# Power_Supply.net
KiCad netlist of a schematic drawn in Altium Designer
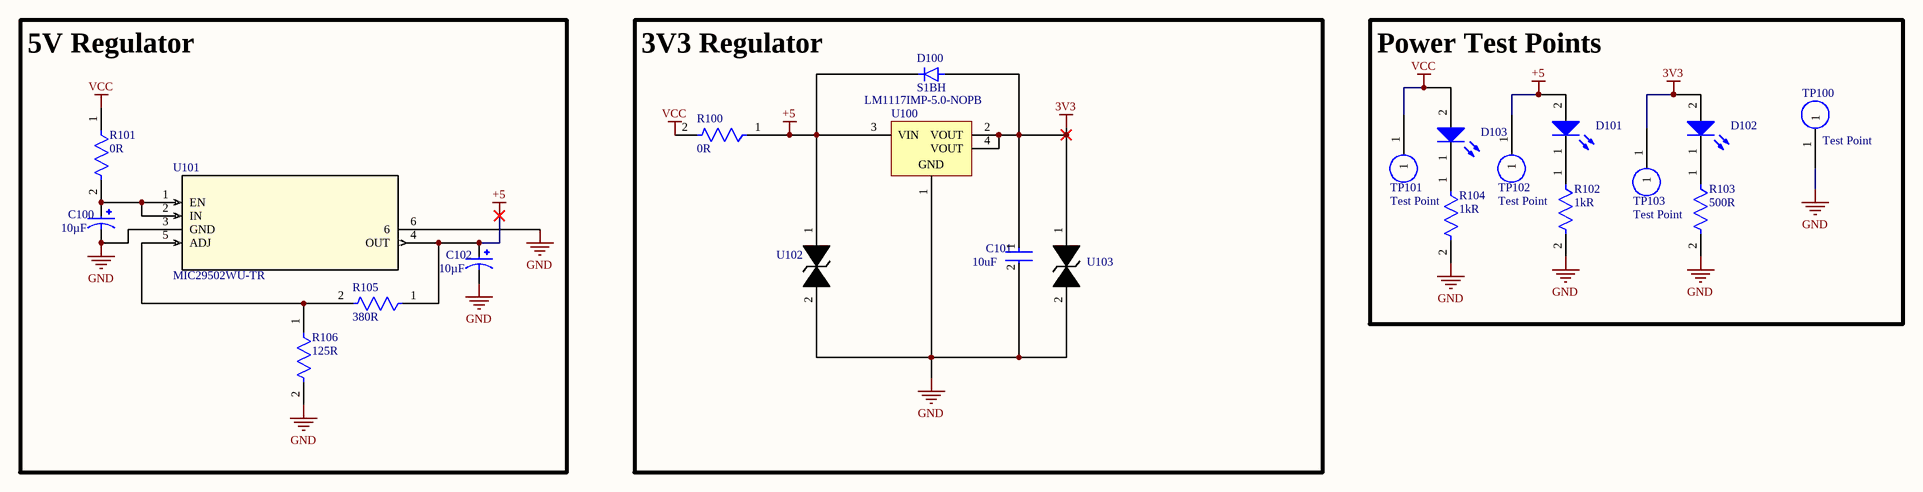
[diagram p0: Power Supply.SchDoc]

(export (version "E")
  (design (tool "Eeschema 10.0.6"))
  (components
    (comp (ref "C100")
      (value "10µF")
      (footprint "CAP_EEEFN1C100R")
      (description "10ÂµF 16V Aluminum Electrolytic Capacitors Radial, Can - SMD 1.35Ohm @ 100kHz 2000 Hrs @ 105Â°C")
      (fields (field (name "DIGI-KEY_PART_NUMBER") "10-EEE-FN1C100RCT-ND") (field (name "MP") "EEEFN1C100R"))
      (libsource (lib "Erich Robb") (part "EEEFN1C100R"))
    )
    (comp (ref "C101")
      (value "GRM21BR61E106KA73L")
      (footprint "FP-GRM21B-0_15-IPC_C")
      (description "Chip Multilayer Ceramic Capacitors for General Purpose, 0805, 10uF, X5R, 15%, 10%, 25V")
      (fields
        (field (name "VOLTAGE") "25V")
        (field (name "CAPACITANCE") "10uF")
        (field (name "TOLERANCE") "10%")
      )
      (libsource (lib "Altium Content Vault") (part "b4654b650e69147ec39a6b967a45e02"))
    )
    (comp (ref "C102")
      (value "10µF")
      (footprint "CAP_EEEFN1C100R")
      (description "10ÂµF 16V Aluminum Electrolytic Capacitors Radial, Can - SMD 1.35Ohm @ 100kHz 2000 Hrs @ 105Â°C")
      (fields (field (name "DIGI-KEY_PART_NUMBER") "10-EEE-FN1C100RCT-ND") (field (name "MP") "EEEFN1C100R"))
      (libsource (lib "Erich Robb") (part "EEEFN1C100R"))
    )
    (comp (ref "D100")
      (value "S1BH")
      (footprint "DIOM4325X250N")
      (libsource (lib "Erich Robb") (part "S1BH"))
    )
    (comp (ref "D101")
      (value "150060BS75000")
      (footprint "WL-SMCW_0603_150060xx75000")
      (description "WL-SMCW Mono-color Chip LED Waterclear, SMT, size 0603, Blue, 3.2V, 140°")
      (fields (field (name "MANUFACTURER") "Wurth Elektronik"))
      (libsource (lib "Erich Robb") (part "150120BS87000"))
    )
    (comp (ref "D102")
      (value "150060BS75000")
      (footprint "WL-SMCW_0603_150060xx75000")
      (description "WL-SMCW Mono-color Chip LED Waterclear, SMT, size 0603, Blue, 3.2V, 140°")
      (fields (field (name "MANUFACTURER") "Wurth Elektronik"))
      (libsource (lib "Erich Robb") (part "150120BS87000"))
    )
    (comp (ref "D103")
      (value "150060BS75000")
      (footprint "WL-SMCW_0603_150060xx75000")
      (description "WL-SMCW Mono-color Chip LED Waterclear, SMT, size 0603, Blue, 3.2V, 140°")
      (fields (field (name "MANUFACTURER") "Wurth Elektronik"))
      (libsource (lib "Erich Robb") (part "150120BS87000"))
    )
    (comp (ref "R100")
      (value "0R")
      (footprint "FP-CPF0603-MFG")
      (description "RES SMD 2.15KΩ 0.1% 1/16W 0603")
      (fields
        (field (name "MANUFACTURER") "TE Connectivity")
        (field (name "OCTOPART") "https://octopart.com/cpf0603b2k15e1-te+connectivity-22739551")
      )
      (libsource (lib "Altium Content Vault") (part "1029c3af85768c4190bb7ad29bc67b5"))
    )
    (comp (ref "R101")
      (value "0R")
      (footprint "FP-CPF0603-MFG")
      (description "RES SMD 2.15KΩ 0.1% 1/16W 0603")
      (fields
        (field (name "MANUFACTURER") "TE Connectivity")
        (field (name "OCTOPART") "https://octopart.com/cpf0603b2k15e1-te+connectivity-22739551")
      )
      (libsource (lib "Altium Content Vault") (part "1029c3af85768c4190bb7ad29bc67b5"))
    )
    (comp (ref "R102")
      (value "1kR")
      (footprint "FP-CPF0603-MFG")
      (description "RES SMD 2.15KΩ 0.1% 1/16W 0603")
      (fields
        (field (name "MANUFACTURER") "TE Connectivity")
        (field (name "OCTOPART") "https://octopart.com/cpf0603b2k15e1-te+connectivity-22739551")
      )
      (libsource (lib "Altium Content Vault") (part "1029c3af85768c4190bb7ad29bc67b5"))
    )
    (comp (ref "R103")
      (value "500R")
      (footprint "FP-CPF0603-MFG")
      (description "RES SMD 2.15KΩ 0.1% 1/16W 0603")
      (fields
        (field (name "MANUFACTURER") "TE Connectivity")
        (field (name "OCTOPART") "https://octopart.com/cpf0603b2k15e1-te+connectivity-22739551")
      )
      (libsource (lib "Altium Content Vault") (part "1029c3af85768c4190bb7ad29bc67b5"))
    )
    (comp (ref "R104")
      (value "1kR")
      (footprint "FP-CPF0603-MFG")
      (description "RES SMD 2.15KΩ 0.1% 1/16W 0603")
      (fields
        (field (name "MANUFACTURER") "TE Connectivity")
        (field (name "OCTOPART") "https://octopart.com/cpf0603b2k15e1-te+connectivity-22739551")
      )
      (libsource (lib "Altium Content Vault") (part "1029c3af85768c4190bb7ad29bc67b5"))
    )
    (comp (ref "R105")
      (value "380R")
      (footprint "FP-CPF0603-MFG")
      (description "RES SMD 2.15KΩ 0.1% 1/16W 0603")
      (fields
        (field (name "MANUFACTURER") "TE Connectivity")
        (field (name "OCTOPART") "https://octopart.com/cpf0603b2k15e1-te+connectivity-22739551")
      )
      (libsource (lib "Altium Content Vault") (part "1029c3af85768c4190bb7ad29bc67b5"))
    )
    (comp (ref "R106")
      (value "125R")
      (footprint "FP-CPF0603-MFG")
      (description "RES SMD 2.15KΩ 0.1% 1/16W 0603")
      (fields
        (field (name "MANUFACTURER") "TE Connectivity")
        (field (name "OCTOPART") "https://octopart.com/cpf0603b2k15e1-te+connectivity-22739551")
      )
      (libsource (lib "Altium Content Vault") (part "1029c3af85768c4190bb7ad29bc67b5"))
    )
    (comp (ref "TP100")
      (value "Test Point")
      (footprint "2mm TP")
      (libsource (lib "Test_Points") (part "Test Point"))
    )
    (comp (ref "TP101")
      (value "Test Point")
      (footprint "2mm TP")
      (libsource (lib "Erich Robb") (part "Test Point"))
    )
    (comp (ref "TP102")
      (value "Test Point")
      (footprint "2mm TP")
      (libsource (lib "Test_Points") (part "Test Point"))
    )
    (comp (ref "TP103")
      (value "Test Point")
      (footprint "2mm TP")
      (libsource (lib "Test_Points") (part "Test Point"))
    )
    (comp (ref "U100")
      (value "LM1117IMP-5.0-NOPB")
      (footprint "DCY0004A_M")
      (fields (field (name "MANUFACTURER") "Texas Instruments"))
      (libsource (lib "Erich Robb") (part "TI-LM1117-N-DCY-4"))
    )
    (comp (ref "U101")
      (value "MIC29502WU-TR")
      (footprint "TO-263-5_MCH")
      (description "No Description Available")
      (libsource (lib "Erich Robb") (part "MIC29502WU-TR"))
    )
    (comp (ref "U102")
      (value "SP1003-01ETG")
      (footprint "SP1003-01ETG_LTF")
      (description "No Description Available")
      (libsource (lib "Erich Robb") (part "SP1003-01ETG"))
    )
    (comp (ref "U103")
      (value "SP1003-01ETG")
      (footprint "SP1003-01ETG_LTF")
      (description "No Description Available")
      (libsource (lib "Erich Robb") (part "SP1003-01ETG"))
    )
  )
  (nets
    (net (code "1") (name "+5") (class "Default")
      (node (ref "C102") (pin "1") (pinfunction "1_1") (pintype "passive"))
      (node (ref "D100") (pin "C") (pinfunction "K_C") (pintype "passive"))
      (node (ref "D101") (pin "2") (pinfunction "A_2") (pintype "passive"))
      (node (ref "R100") (pin "1") (pinfunction "1_1") (pintype "passive"))
      (node (ref "R105") (pin "1") (pinfunction "1_1") (pintype "passive"))
      (node (ref "TP102") (pin "1") (pinfunction "1_1") (pintype "passive"))
      (node (ref "U100") (pin "3") (pinfunction "VIN_3") (pintype "power_in"))
      (node (ref "U101") (pin "4") (pinfunction "OUT_4") (pintype "output"))
      (node (ref "U102") (pin "1") (pinfunction "1_1") (pintype "passive"))
    )
    (net (code "2") (name "3V3") (class "Default")
      (node (ref "C101") (pin "1") (pinfunction "1_1") (pintype "passive"))
      (node (ref "D100") (pin "A") (pinfunction "A_A") (pintype "passive"))
      (node (ref "D102") (pin "2") (pinfunction "A_2") (pintype "passive"))
      (node (ref "TP103") (pin "1") (pinfunction "1_1") (pintype "passive"))
      (node (ref "U100") (pin "2") (pinfunction "VOUT_2") (pintype "power_in"))
      (node (ref "U100") (pin "4") (pinfunction "VOUT_4") (pintype "power_in"))
      (node (ref "U103") (pin "1") (pinfunction "1_1") (pintype "passive"))
    )
    (net (code "3") (name "GND") (class "Default")
      (node (ref "C100") (pin "2") (pinfunction "2_2") (pintype "passive"))
      (node (ref "C101") (pin "2") (pinfunction "2_2") (pintype "passive"))
      (node (ref "C102") (pin "2") (pinfunction "2_2") (pintype "passive"))
      (node (ref "R102") (pin "2") (pinfunction "2_2") (pintype "passive"))
      (node (ref "R103") (pin "2") (pinfunction "2_2") (pintype "passive"))
      (node (ref "R104") (pin "2") (pinfunction "2_2") (pintype "passive"))
      (node (ref "R106") (pin "2") (pinfunction "2_2") (pintype "passive"))
      (node (ref "TP100") (pin "1") (pinfunction "1_1") (pintype "passive"))
      (node (ref "U100") (pin "1") (pinfunction "GND_1") (pintype "power_in"))
      (node (ref "U101") (pin "3") (pinfunction "GND_3") (pintype "power_in"))
      (node (ref "U101") (pin "6") (pinfunction "6_6") (pintype "passive"))
      (node (ref "U102") (pin "2") (pinfunction "2_2") (pintype "passive"))
      (node (ref "U103") (pin "2") (pinfunction "2_2") (pintype "passive"))
    )
    (net (code "4") (name "Net-(D101-K)") (class "Default")
      (node (ref "D101") (pin "1") (pinfunction "K_1") (pintype "passive"))
      (node (ref "R102") (pin "1") (pinfunction "1_1") (pintype "passive"))
    )
    (net (code "5") (name "Net-(D102-K)") (class "Default")
      (node (ref "D102") (pin "1") (pinfunction "K_1") (pintype "passive"))
      (node (ref "R103") (pin "1") (pinfunction "1_1") (pintype "passive"))
    )
    (net (code "6") (name "Net-(D103-K)") (class "Default")
      (node (ref "D103") (pin "1") (pinfunction "K_1") (pintype "passive"))
      (node (ref "R104") (pin "1") (pinfunction "1_1") (pintype "passive"))
    )
    (net (code "7") (name "Net-(U101-ADJ)") (class "Default")
      (node (ref "R105") (pin "2") (pinfunction "2_2") (pintype "passive"))
      (node (ref "R106") (pin "1") (pinfunction "1_1") (pintype "passive"))
      (node (ref "U101") (pin "5") (pinfunction "ADJ_5") (pintype "input"))
    )
    (net (code "8") (name "Net-(U101-EN)") (class "Default")
      (node (ref "C100") (pin "1") (pinfunction "1_1") (pintype "passive"))
      (node (ref "R101") (pin "2") (pinfunction "2_2") (pintype "passive"))
      (node (ref "U101") (pin "1") (pinfunction "EN_1") (pintype "input"))
      (node (ref "U101") (pin "2") (pinfunction "IN_2") (pintype "input"))
    )
    (net (code "9") (name "VCC") (class "Default")
      (node (ref "D103") (pin "2") (pinfunction "A_2") (pintype "passive"))
      (node (ref "R100") (pin "2") (pinfunction "2_2") (pintype "passive"))
      (node (ref "R101") (pin "1") (pinfunction "1_1") (pintype "passive"))
      (node (ref "TP101") (pin "1") (pinfunction "1_1") (pintype "passive"))
    )
  )
)
